# BQ25616_EvalBoard.net
KiCad netlist of a schematic drawn in EAGLE
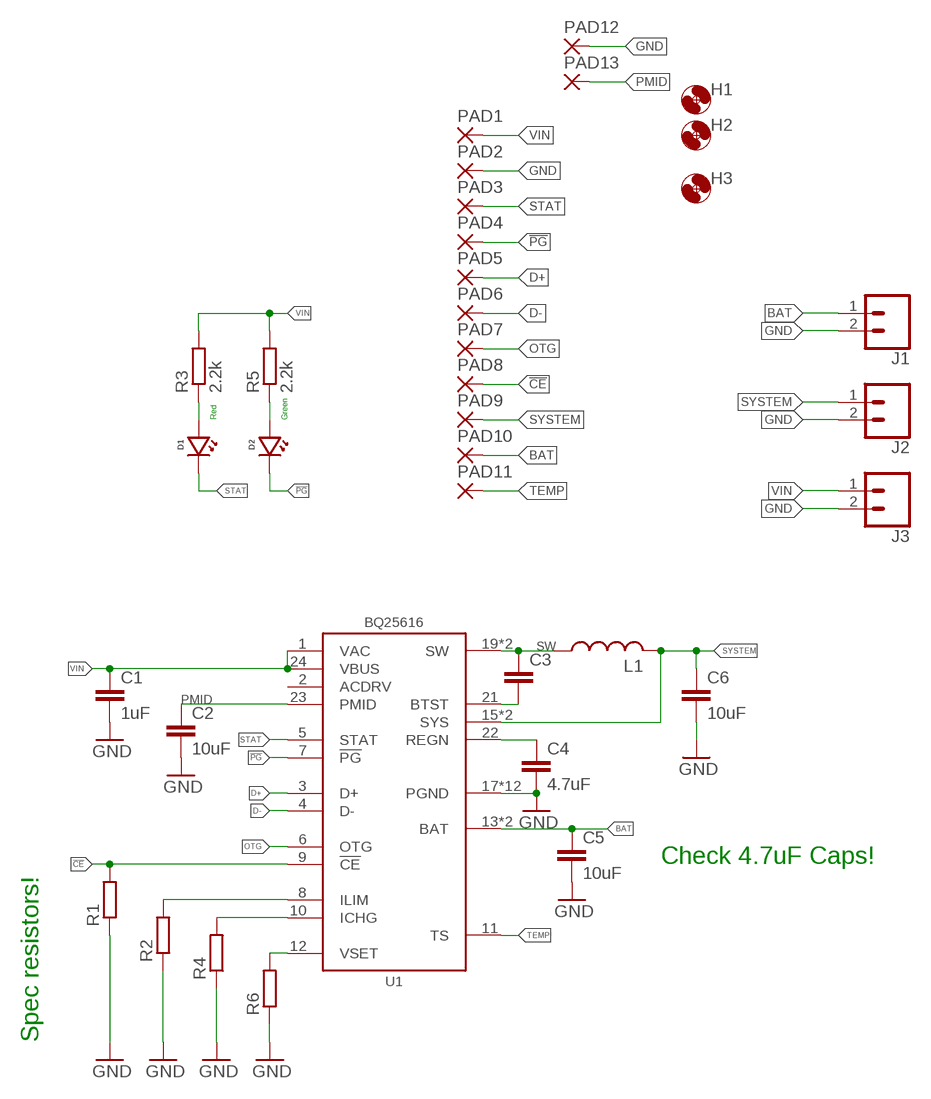
[diagram p0: schematic, sheet 1]

(export (version "E")
  (design (tool "Eeschema 10.0.6"))
  (components
    (comp (ref "C1")
      (value "1uF")
      (footprint "eagle-import:C0603")
      (fields (field (name "MF") "Yaiyo Yuden") (field (name "MPN") "EMK107BJ105KA-T"))
      (libsource (lib "eagle-import") (part "C-EUC06031UF"))
    )
    (comp (ref "C2")
      (value "10uF")
      (footprint "eagle-import:C0805")
      (fields (field (name "MF") "Murata") (field (name "MPN") "GRM21BR61C106KE15K"))
      (libsource (lib "eagle-import") (part "C-EUC080510UF"))
    )
    (comp (ref "C3")
      (value "C-EUC0603")
      (footprint "eagle-import:C0603")
      (libsource (lib "eagle-import") (part "C-EUC0603"))
    )
    (comp (ref "C4")
      (value "4.7uF")
      (footprint "eagle-import:C0805")
      (fields (field (name "MF") "Kemet") (field (name "MPN") "C0805C475K4RACTU"))
      (libsource (lib "eagle-import") (part "C-EUC08054.7UF"))
    )
    (comp (ref "C5")
      (value "10uF")
      (footprint "eagle-import:C0805")
      (fields (field (name "MF") "Murata") (field (name "MPN") "GRM21BR61C106KE15K"))
      (libsource (lib "eagle-import") (part "C-EUC080510UF"))
    )
    (comp (ref "C6")
      (value "10uF")
      (footprint "eagle-import:C0805")
      (fields (field (name "MF") "Murata") (field (name "MPN") "GRM21BR61C106KE15K"))
      (libsource (lib "eagle-import") (part "C-EUC080510UF"))
    )
    (comp (ref "D1")
      (value "LEDGREEN0603")
      (footprint "eagle-import:LED_0603")
      (fields (field (name "MF") "Wurth") (field (name "MPN") "150060GS75000"))
      (libsource (lib "eagle-import") (part "LED0603GREEN"))
    )
    (comp (ref "D2")
      (value "LEDRED0603")
      (footprint "eagle-import:LED_0603")
      (fields (field (name "MF") "Wurth") (field (name "MPN") "150060RS75000"))
      (libsource (lib "eagle-import") (part "LED0603RED"))
    )
    (comp (ref "H1")
      (value "MOUNTING_HOLE2_NP")
      (footprint "eagle-import:2_56")
      (fields (field (name "MPN") "DNP"))
      (libsource (lib "eagle-import") (part "MOUNTING_HOLE2_NP"))
    )
    (comp (ref "H2")
      (value "MOUNTING_HOLE2_NP")
      (footprint "eagle-import:2_56")
      (fields (field (name "MPN") "DNP"))
      (libsource (lib "eagle-import") (part "MOUNTING_HOLE2_NP"))
    )
    (comp (ref "H3")
      (value "MOUNTING_HOLE2_NP")
      (footprint "eagle-import:2_56")
      (fields (field (name "MPN") "DNP"))
      (libsource (lib "eagle-import") (part "MOUNTING_HOLE2_NP"))
    )
    (comp (ref "J1")
      (value "CONN_023.5MM_ROUND_RESTRICT")
      (footprint "eagle-import:SCREWTERMINAL-3.5MM-2_ROUND_RESTRICT")
      (fields (field (name "MF") "On Shore") (field (name "MPN") "OSTTE020161"))
      (libsource (lib "eagle-import") (part "CONN_023.5MM_ROUND_RESTRICT"))
    )
    (comp (ref "J2")
      (value "CONN_023.5MM_ROUND_RESTRICT")
      (footprint "eagle-import:SCREWTERMINAL-3.5MM-2_ROUND_RESTRICT")
      (fields (field (name "MF") "On Shore") (field (name "MPN") "OSTTE020161"))
      (libsource (lib "eagle-import") (part "CONN_023.5MM_ROUND_RESTRICT"))
    )
    (comp (ref "J3")
      (value "CONN_023.5MM_ROUND_RESTRICT")
      (footprint "eagle-import:SCREWTERMINAL-3.5MM-2_ROUND_RESTRICT")
      (fields (field (name "MF") "On Shore") (field (name "MPN") "OSTTE020161"))
      (libsource (lib "eagle-import") (part "CONN_023.5MM_ROUND_RESTRICT"))
    )
    (comp (ref "L1")
      (value "INDUCTORMAIA_4.1X4.1")
      (footprint "eagle-import:WE-MAIA(4.1X4.1)")
      (libsource (lib "eagle-import") (part "INDUCTORMAIA_4.1X4.1"))
    )
    (comp (ref "PAD1")
      (value "SMD1,27")
      (footprint "eagle-import:SMD1,27-2,54")
      (fields (field (name "MPN") "DNP"))
      (libsource (lib "eagle-import") (part "SMD1,27"))
    )
    (comp (ref "PAD2")
      (value "SMD1,27")
      (footprint "eagle-import:SMD1,27-2,54")
      (fields (field (name "MPN") "DNP"))
      (libsource (lib "eagle-import") (part "SMD1,27"))
    )
    (comp (ref "PAD3")
      (value "SMD1,27")
      (footprint "eagle-import:SMD1,27-2,54")
      (fields (field (name "MPN") "DNP"))
      (libsource (lib "eagle-import") (part "SMD1,27"))
    )
    (comp (ref "PAD4")
      (value "SMD1,27")
      (footprint "eagle-import:SMD1,27-2,54")
      (fields (field (name "MPN") "DNP"))
      (libsource (lib "eagle-import") (part "SMD1,27"))
    )
    (comp (ref "PAD5")
      (value "SMD1,27")
      (footprint "eagle-import:SMD1,27-2,54")
      (fields (field (name "MPN") "DNP"))
      (libsource (lib "eagle-import") (part "SMD1,27"))
    )
    (comp (ref "PAD6")
      (value "SMD1,27")
      (footprint "eagle-import:SMD1,27-2,54")
      (fields (field (name "MPN") "DNP"))
      (libsource (lib "eagle-import") (part "SMD1,27"))
    )
    (comp (ref "PAD7")
      (value "SMD1,27")
      (footprint "eagle-import:SMD1,27-2,54")
      (fields (field (name "MPN") "DNP"))
      (libsource (lib "eagle-import") (part "SMD1,27"))
    )
    (comp (ref "PAD8")
      (value "SMD1,27")
      (footprint "eagle-import:SMD1,27-2,54")
      (fields (field (name "MPN") "DNP"))
      (libsource (lib "eagle-import") (part "SMD1,27"))
    )
    (comp (ref "PAD9")
      (value "SMD1,27")
      (footprint "eagle-import:SMD1,27-2,54")
      (fields (field (name "MPN") "DNP"))
      (libsource (lib "eagle-import") (part "SMD1,27"))
    )
    (comp (ref "PAD10")
      (value "SMD1,27")
      (footprint "eagle-import:SMD1,27-2,54")
      (fields (field (name "MPN") "DNP"))
      (libsource (lib "eagle-import") (part "SMD1,27"))
    )
    (comp (ref "PAD11")
      (value "SMD1,27")
      (footprint "eagle-import:SMD1,27-2,54")
      (fields (field (name "MPN") "DNP"))
      (libsource (lib "eagle-import") (part "SMD1,27"))
    )
    (comp (ref "PAD12")
      (value "SMD1,27")
      (footprint "eagle-import:SMD1,27-2,54")
      (fields (field (name "MPN") "DNP"))
      (libsource (lib "eagle-import") (part "SMD1,27"))
    )
    (comp (ref "PAD13")
      (value "SMD1,27")
      (footprint "eagle-import:SMD1,27-2,54")
      (fields (field (name "MPN") "DNP"))
      (libsource (lib "eagle-import") (part "SMD1,27"))
    )
    (comp (ref "R1")
      (value "R-EU_R0603")
      (footprint "eagle-import:R0603")
      (fields (field (name "MF") "Yageo"))
      (libsource (lib "eagle-import") (part "R-EU_R0603"))
    )
    (comp (ref "R2")
      (value "R-EU_R0603")
      (footprint "eagle-import:R0603")
      (fields (field (name "MF") "Yageo"))
      (libsource (lib "eagle-import") (part "R-EU_R0603"))
    )
    (comp (ref "R3")
      (value "2.2k")
      (footprint "eagle-import:R0603")
      (fields (field (name "MF") "Yageo") (field (name "MPN") "RC0603FR-072K2L"))
      (libsource (lib "eagle-import") (part "R-EU_R06032.2K"))
    )
    (comp (ref "R4")
      (value "R-EU_R0603")
      (footprint "eagle-import:R0603")
      (fields (field (name "MF") "Yageo"))
      (libsource (lib "eagle-import") (part "R-EU_R0603"))
    )
    (comp (ref "R5")
      (value "2.2k")
      (footprint "eagle-import:R0603")
      (fields (field (name "MF") "Yageo") (field (name "MPN") "RC0603FR-072K2L"))
      (libsource (lib "eagle-import") (part "R-EU_R06032.2K"))
    )
    (comp (ref "R6")
      (value "R-EU_R0603")
      (footprint "eagle-import:R0603")
      (fields (field (name "MF") "Yageo"))
      (libsource (lib "eagle-import") (part "R-EU_R0603"))
    )
    (comp (ref "U1")
      (value "BQ25616")
      (footprint "eagle-import:QFN24_POWER")
      (fields (field (name "MF") "TI") (field (name "MPN") "BQ25616RTWR"))
      (libsource (lib "eagle-import") (part "BQ25616"))
    )
  )
  (nets
    (net (code "1") (name "/SW") (class "Default")
      (node (ref "C3") (pin "1") (pinfunction "1_1") (pintype "passive"))
      (node (ref "L1") (pin "P$1") (pinfunction "1_P$1") (pintype "passive"))
      (node (ref "U1") (pin "19") (pinfunction "SW_19") (pintype "power_in"))
      (node (ref "U1") (pin "20") (pinfunction "SW_20") (pintype "power_in"))
    )
    (net (code "2") (name "/~{CE}") (class "Default")
      (node (ref "PAD8") (pin "1") (pinfunction "P_1") (pintype "passive"))
      (node (ref "R1") (pin "2") (pinfunction "2_2") (pintype "passive"))
      (node (ref "U1") (pin "9") (pinfunction "~{CE}_9") (pintype "input"))
    )
    (net (code "3") (name "/~{PG}") (class "Default")
      (node (ref "D2") (pin "CATHODE") (pinfunction "CATHODE_CATHODE") (pintype "power_in"))
      (node (ref "PAD4") (pin "1") (pinfunction "P_1") (pintype "passive"))
      (node (ref "U1") (pin "7") (pinfunction "~{PG}_7") (pintype "output"))
    )
    (net (code "4") (name "BAT") (class "Default")
      (node (ref "C5") (pin "1") (pinfunction "1_1") (pintype "passive"))
      (node (ref "J1") (pin "1") (pinfunction "1_1") (pintype "passive"))
      (node (ref "PAD10") (pin "1") (pinfunction "P_1") (pintype "passive"))
      (node (ref "U1") (pin "13") (pinfunction "BAT_13") (pintype "power_in"))
      (node (ref "U1") (pin "14") (pinfunction "BAT_14") (pintype "power_in"))
    )
    (net (code "5") (name "D+") (class "Default")
      (node (ref "PAD5") (pin "1") (pinfunction "P_1") (pintype "passive"))
      (node (ref "U1") (pin "3") (pinfunction "D+_3") (pintype "bidirectional"))
    )
    (net (code "6") (name "D-") (class "Default")
      (node (ref "PAD6") (pin "1") (pinfunction "P_1") (pintype "passive"))
      (node (ref "U1") (pin "4") (pinfunction "D-_4") (pintype "bidirectional"))
    )
    (net (code "7") (name "GND") (class "Default")
      (node (ref "C1") (pin "2") (pinfunction "2_2") (pintype "passive"))
      (node (ref "C2") (pin "2") (pinfunction "2_2") (pintype "passive"))
      (node (ref "C4") (pin "2") (pinfunction "2_2") (pintype "passive"))
      (node (ref "C5") (pin "2") (pinfunction "2_2") (pintype "passive"))
      (node (ref "C6") (pin "2") (pinfunction "2_2") (pintype "passive"))
      (node (ref "J1") (pin "2") (pinfunction "2_2") (pintype "passive"))
      (node (ref "J2") (pin "2") (pinfunction "2_2") (pintype "passive"))
      (node (ref "J3") (pin "2") (pinfunction "2_2") (pintype "passive"))
      (node (ref "PAD12") (pin "1") (pinfunction "P_1") (pintype "passive"))
      (node (ref "PAD2") (pin "1") (pinfunction "P_1") (pintype "passive"))
      (node (ref "R1") (pin "1") (pinfunction "1_1") (pintype "passive"))
      (node (ref "R2") (pin "1") (pinfunction "1_1") (pintype "passive"))
      (node (ref "R4") (pin "1") (pinfunction "1_1") (pintype "passive"))
      (node (ref "R6") (pin "1") (pinfunction "1_1") (pintype "passive"))
      (node (ref "U1") (pin "17") (pinfunction "PGND_17") (pintype "power_in"))
      (node (ref "U1") (pin "18") (pinfunction "PGND_18") (pintype "power_in"))
      (node (ref "U1") (pin "EP") (pinfunction "PGND_EP") (pintype "power_in"))
      (node (ref "U1") (pin "EP@1") (pinfunction "PGND_EP@1") (pintype "power_in"))
      (node (ref "U1") (pin "EP@2") (pinfunction "PGND_EP@2") (pintype "power_in"))
      (node (ref "U1") (pin "EP@3") (pinfunction "PGND_EP@3") (pintype "power_in"))
      (node (ref "U1") (pin "EP@4") (pinfunction "PGND_EP@4") (pintype "power_in"))
      (node (ref "U1") (pin "EP@5") (pinfunction "PGND_EP@5") (pintype "power_in"))
      (node (ref "U1") (pin "EP@6") (pinfunction "PGND_EP@6") (pintype "power_in"))
      (node (ref "U1") (pin "EP@7") (pinfunction "PGND_EP@7") (pintype "power_in"))
      (node (ref "U1") (pin "EP@8") (pinfunction "PGND_EP@8") (pintype "power_in"))
      (node (ref "U1") (pin "EP@9") (pinfunction "PGND_EP@9") (pintype "power_in"))
    )
    (net (code "8") (name "Net-(D1-PadANODE)") (class "Default")
      (node (ref "D1") (pin "ANODE") (pinfunction "ANODE_ANODE") (pintype "power_in"))
      (node (ref "R3") (pin "1") (pinfunction "1_1") (pintype "passive"))
    )
    (net (code "9") (name "Net-(D2-PadANODE)") (class "Default")
      (node (ref "D2") (pin "ANODE") (pinfunction "ANODE_ANODE") (pintype "power_in"))
      (node (ref "R5") (pin "1") (pinfunction "1_1") (pintype "passive"))
    )
    (net (code "10") (name "Net-(U1-BTST)") (class "Default")
      (node (ref "C3") (pin "2") (pinfunction "2_2") (pintype "passive"))
      (node (ref "U1") (pin "21") (pinfunction "BTST_21") (pintype "power_in"))
    )
    (net (code "11") (name "Net-(U1-ICHG)") (class "Default")
      (node (ref "R4") (pin "2") (pinfunction "2_2") (pintype "passive"))
      (node (ref "U1") (pin "10") (pinfunction "ICHG_10") (pintype "input"))
    )
    (net (code "12") (name "Net-(U1-ILIM)") (class "Default")
      (node (ref "R2") (pin "2") (pinfunction "2_2") (pintype "passive"))
      (node (ref "U1") (pin "8") (pinfunction "ILIM_8") (pintype "input"))
    )
    (net (code "13") (name "Net-(U1-REGN)") (class "Default")
      (node (ref "C4") (pin "1") (pinfunction "1_1") (pintype "passive"))
      (node (ref "U1") (pin "22") (pinfunction "REGN_22") (pintype "bidirectional"))
    )
    (net (code "14") (name "Net-(U1-VSET)") (class "Default")
      (node (ref "R6") (pin "2") (pinfunction "2_2") (pintype "passive"))
      (node (ref "U1") (pin "12") (pinfunction "VSET_12") (pintype "input"))
    )
    (net (code "15") (name "OTG") (class "Default")
      (node (ref "PAD7") (pin "1") (pinfunction "P_1") (pintype "passive"))
      (node (ref "U1") (pin "6") (pinfunction "OTG_6") (pintype "input"))
    )
    (net (code "16") (name "PMID") (class "Default")
      (node (ref "C2") (pin "1") (pinfunction "1_1") (pintype "passive"))
      (node (ref "PAD13") (pin "1") (pinfunction "P_1") (pintype "passive"))
      (node (ref "U1") (pin "23") (pinfunction "PMID_23") (pintype "power_in"))
    )
    (net (code "17") (name "STAT") (class "Default")
      (node (ref "D1") (pin "CATHODE") (pinfunction "CATHODE_CATHODE") (pintype "power_in"))
      (node (ref "PAD3") (pin "1") (pinfunction "P_1") (pintype "passive"))
      (node (ref "U1") (pin "5") (pinfunction "STAT_5") (pintype "output"))
    )
    (net (code "18") (name "SYSTEM") (class "Default")
      (node (ref "C6") (pin "1") (pinfunction "1_1") (pintype "passive"))
      (node (ref "J2") (pin "1") (pinfunction "1_1") (pintype "passive"))
      (node (ref "L1") (pin "P$2") (pinfunction "2_P$2") (pintype "passive"))
      (node (ref "PAD9") (pin "1") (pinfunction "P_1") (pintype "passive"))
      (node (ref "U1") (pin "15") (pinfunction "SYS_15") (pintype "power_in"))
      (node (ref "U1") (pin "16") (pinfunction "SYS_16") (pintype "power_in"))
    )
    (net (code "19") (name "TEMP") (class "Default")
      (node (ref "PAD11") (pin "1") (pinfunction "P_1") (pintype "passive"))
      (node (ref "U1") (pin "11") (pinfunction "TS_11") (pintype "input"))
    )
    (net (code "20") (name "VIN") (class "Default")
      (node (ref "C1") (pin "1") (pinfunction "1_1") (pintype "passive"))
      (node (ref "J3") (pin "1") (pinfunction "1_1") (pintype "passive"))
      (node (ref "PAD1") (pin "1") (pinfunction "P_1") (pintype "passive"))
      (node (ref "R3") (pin "2") (pinfunction "2_2") (pintype "passive"))
      (node (ref "R5") (pin "2") (pinfunction "2_2") (pintype "passive"))
      (node (ref "U1") (pin "1") (pinfunction "VAC_1") (pintype "power_in"))
      (node (ref "U1") (pin "24") (pinfunction "VBUS_24") (pintype "bidirectional"))
    )
    (net (code "21") (name "unconnected-(U1-ACDRV-Pad2)") (class "Default")
      (node (ref "U1") (pin "2") (pinfunction "ACDRV_2") (pintype "output"))
    )
  )
)
